# main.net
KiCad netlist of a schematic drawn in Altium Designer
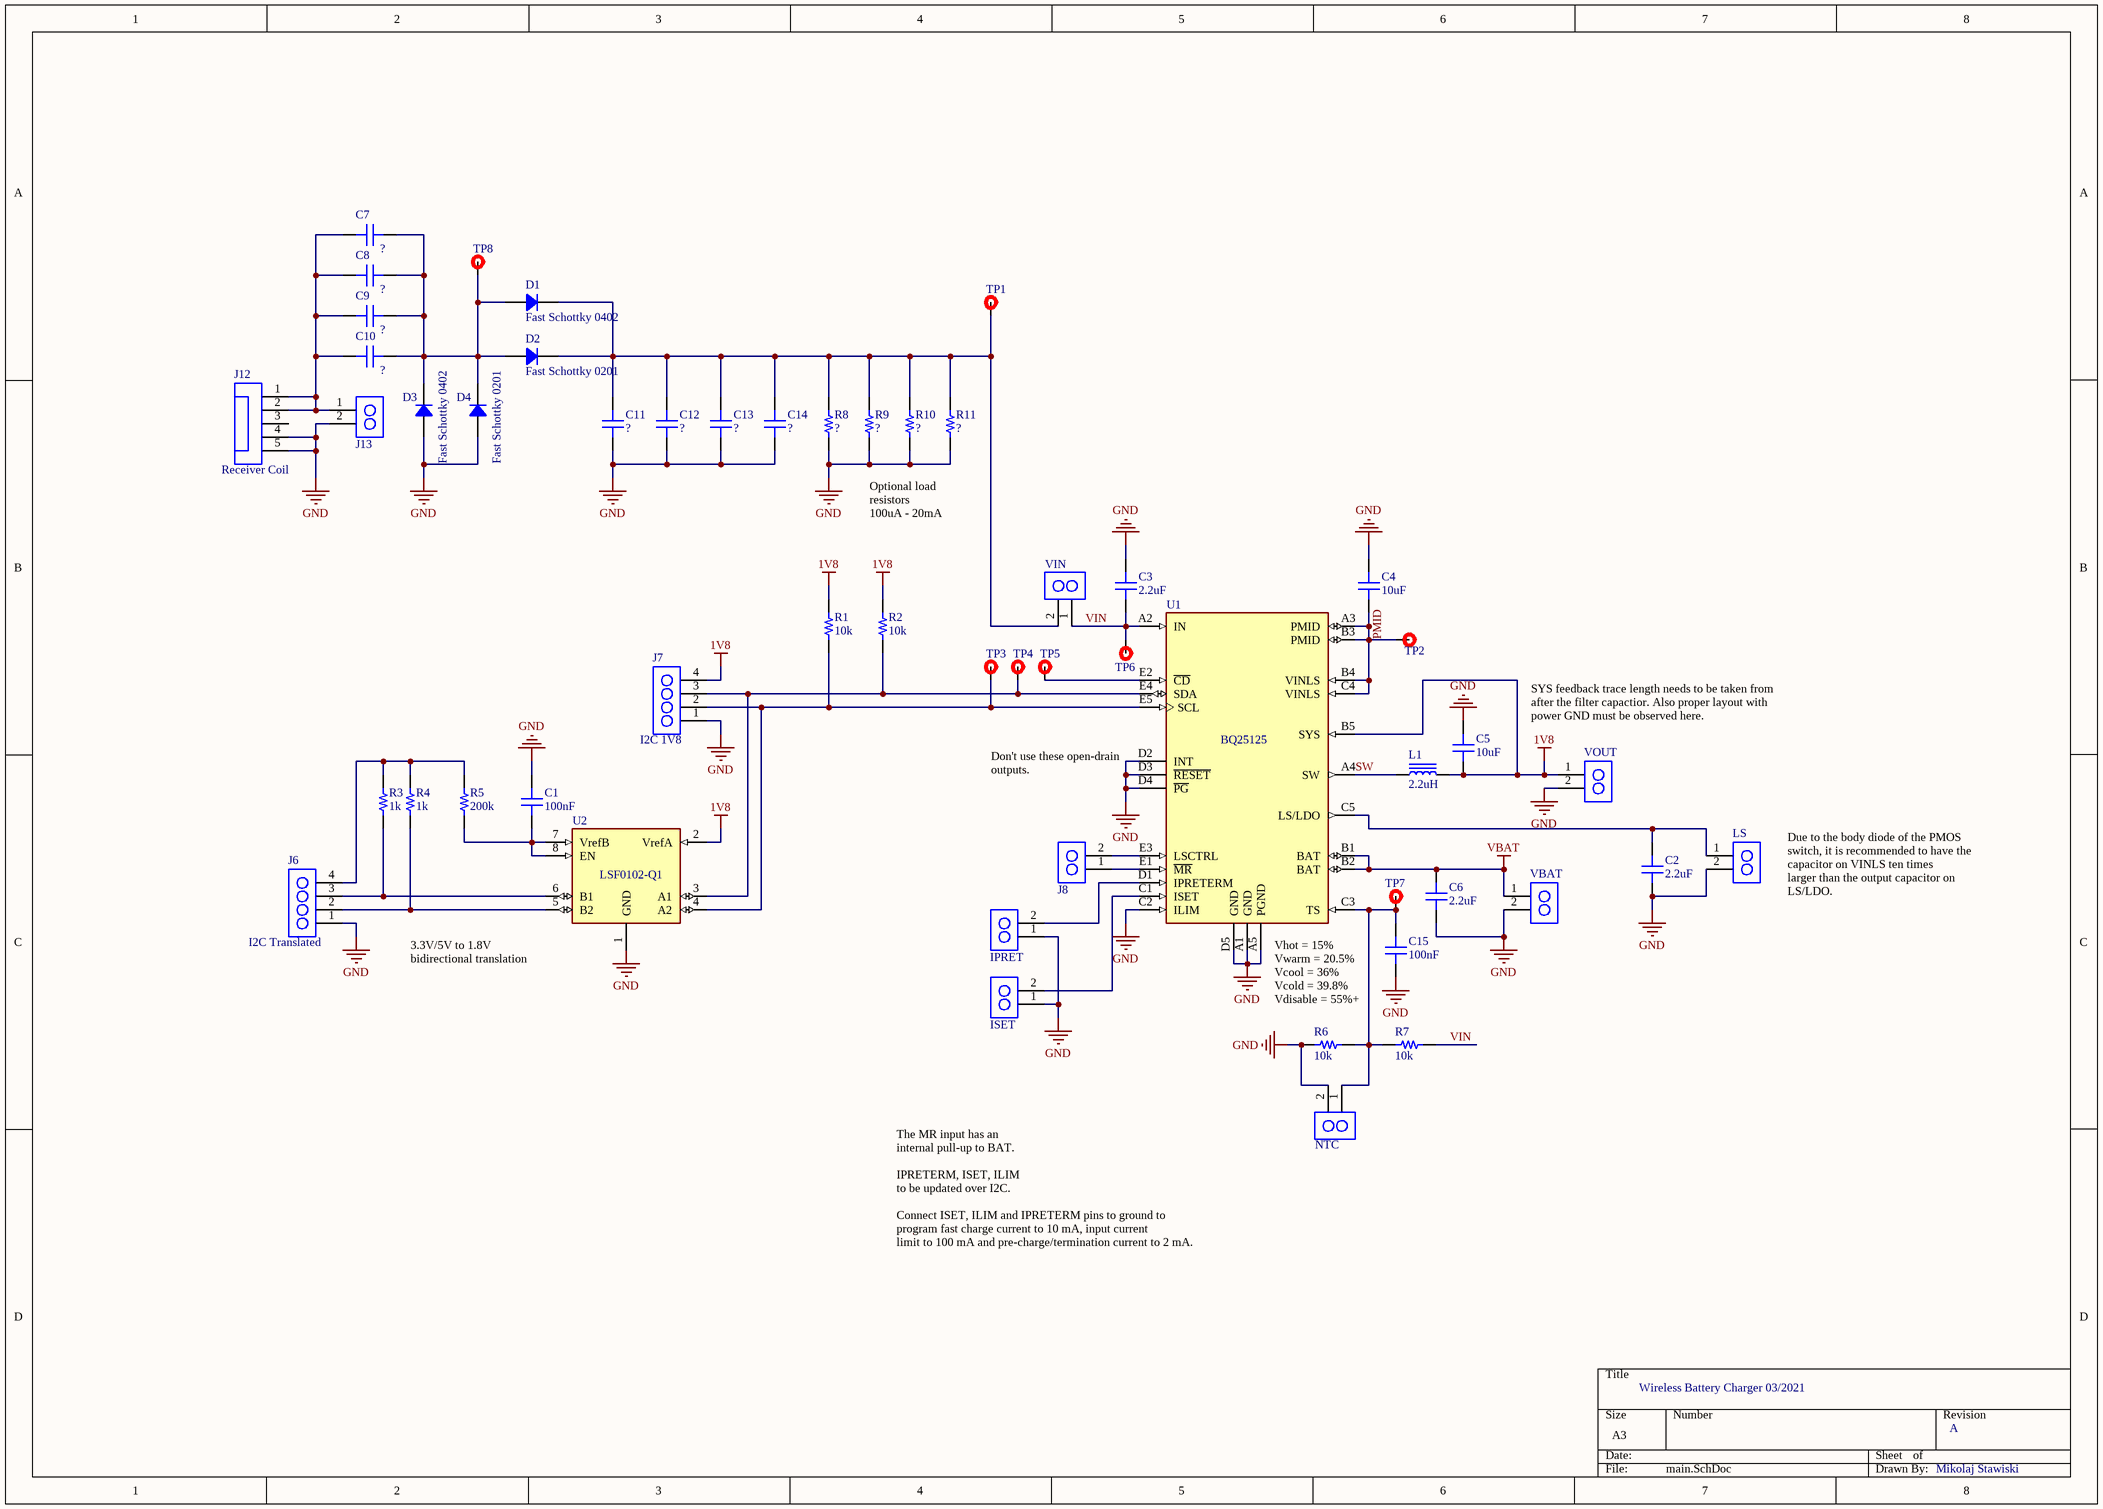
[diagram p0: main.SchDoc]

(export (version "E")
  (design (tool "Eeschema 10.0.6"))
  (components
    (comp (ref "C1")
      (value "100nF")
      (footprint "SMD_CAPACITOR_0603")
      (description "Capacitor SMT 0603")
      (libsource (lib "common") (part "CAPACITOR_0603"))
    )
    (comp (ref "C2")
      (value "2.2uF")
      (footprint "SMD_CAPACITOR_0402")
      (description "Ceramic Capacitor 2.2uF 20% 6.3V X5R 0402")
      (fields (field (name "PART NUMBER") "GRM155R60J225ME15D") (field (name "MANUFACTURER") "Murata"))
      (libsource (lib "common") (part "CAPACITOR_0402"))
    )
    (comp (ref "C3")
      (value "2.2uF")
      (footprint "SMD_CAPACITOR_0402")
      (description "Ceramic Capacitor 2.2uF 20% 6.3V X5R 0402")
      (fields (field (name "PART NUMBER") "GRM155R60J225ME15D") (field (name "MANUFACTURER") "Murata"))
      (libsource (lib "common") (part "CAPACITOR_0402"))
    )
    (comp (ref "C4")
      (value "10uF")
      (footprint "SMD_CAPACITOR_0402")
      (description "Ceramic Capacitor 10uF 20% 10V X5R 0402")
      (fields (field (name "PART NUMBER") "CL05A106MP5NUNC") (field (name "MANUFACTURER") "Samsung"))
      (libsource (lib "common") (part "CAPACITOR_0402"))
    )
    (comp (ref "C5")
      (value "10uF")
      (footprint "SMD_CAPACITOR_0402")
      (description "Ceramic Capacitor 10uF 20% 10V X5R 0402")
      (fields (field (name "PART NUMBER") "CL05A106MP5NUNC") (field (name "MANUFACTURER") "Samsung"))
      (libsource (lib "common") (part "CAPACITOR_0402"))
    )
    (comp (ref "C6")
      (value "2.2uF")
      (footprint "SMD_CAPACITOR_0402")
      (description "Ceramic Capacitor 2.2uF 20% 6.3V X5R 0402")
      (fields (field (name "PART NUMBER") "GRM155R60J225ME15D") (field (name "MANUFACTURER") "Murata"))
      (libsource (lib "common") (part "CAPACITOR_0402"))
    )
    (comp (ref "C7")
      (value "?")
      (footprint "SMD_CAPACITOR_0402")
      (description "Ceramic Capacitor 10V X5R 0402")
      (libsource (lib "common") (part "CAPACITOR_0402"))
    )
    (comp (ref "C8")
      (value "?")
      (footprint "SMD_CAPACITOR_0402")
      (description "Ceramic Capacitor 10V X5R 0402")
      (libsource (lib "common") (part "CAPACITOR_0402"))
    )
    (comp (ref "C9")
      (value "?")
      (footprint "SMD_CAPACITOR_0402")
      (description "Ceramic Capacitor 10V X5R 0402")
      (libsource (lib "common") (part "CAPACITOR_0402"))
    )
    (comp (ref "C10")
      (value "?")
      (footprint "SMD_CAPACITOR_0402")
      (description "Ceramic Capacitor 10V X5R 0402")
      (libsource (lib "common") (part "CAPACITOR_0402"))
    )
    (comp (ref "C11")
      (value "?")
      (footprint "SMD_CAPACITOR_0402")
      (description "Ceramic Capacitor 10V X5R 0402")
      (libsource (lib "common") (part "CAPACITOR_0402"))
    )
    (comp (ref "C12")
      (value "?")
      (footprint "SMD_CAPACITOR_0402")
      (description "Ceramic Capacitor 10V X5R 0402")
      (libsource (lib "common") (part "CAPACITOR_0402"))
    )
    (comp (ref "C13")
      (value "?")
      (footprint "SMD_CAPACITOR_0402")
      (description "Ceramic Capacitor 10V X5R 0402")
      (libsource (lib "common") (part "CAPACITOR_0402"))
    )
    (comp (ref "C14")
      (value "?")
      (footprint "SMD_CAPACITOR_0402")
      (description "Ceramic Capacitor 10V X5R 0402")
      (libsource (lib "common") (part "CAPACITOR_0402"))
    )
    (comp (ref "C15")
      (value "100nF")
      (footprint "SMD_CAPACITOR_0201")
      (description "Capacitor SMT 0201")
      (libsource (lib "common") (part "CAPACITOR_0201"))
    )
    (comp (ref "D1")
      (value "Fast Schottky 0402")
      (footprint "CLP1006-2L")
      (description "Diode SMT 0402")
      (fields (field (name "PART NUMBER") "VSKY05301006") (field (name "MANUFACTURER") "Vishay"))
      (libsource (lib "common") (part "DIODE_0402"))
    )
    (comp (ref "D2")
      (value "Fast Schottky 0201")
      (footprint "CLP0603-2M")
      (description "Diode SMT 0201")
      (fields (field (name "PART NUMBER") "VSKY02300603") (field (name "MANUFACTURER") "Vishay"))
      (libsource (lib "common") (part "DIODE_0201"))
    )
    (comp (ref "D3")
      (value "Fast Schottky 0402")
      (footprint "CLP1006-2L")
      (description "Diode SMT 0402")
      (fields (field (name "PART NUMBER") "VSKY05301006") (field (name "MANUFACTURER") "Vishay"))
      (libsource (lib "common") (part "DIODE_0402"))
    )
    (comp (ref "D4")
      (value "Fast Schottky 0201")
      (footprint "CLP0603-2M")
      (description "Diode SMT 0201")
      (fields (field (name "PART NUMBER") "VSKY02300603") (field (name "MANUFACTURER") "Vishay"))
      (libsource (lib "common") (part "DIODE_0201"))
    )
    (comp (ref "IPRET")
      (value "*")
      (footprint "HEADER_2PIN_0022272021")
      (description "Connector 2-pin generic")
      (libsource (lib "common") (part "CONN_2PIN"))
    )
    (comp (ref "ISET")
      (value "*")
      (footprint "HEADER_2PIN_0022272021")
      (description "Connector 2-pin generic")
      (libsource (lib "common") (part "CONN_2PIN"))
    )
    (comp (ref "J6")
      (value "I2C Translated")
      (footprint "HEADER_4PIN_0022272041")
      (description "Connector 4-pin generic")
      (libsource (lib "common") (part "CONN_4PIN"))
    )
    (comp (ref "J7")
      (value "I2C 1V8")
      (footprint "HEADER_4PIN_0022272041")
      (description "Connector 4-pin generic")
      (libsource (lib "common") (part "CONN_4PIN"))
    )
    (comp (ref "J8")
      (value "*")
      (footprint "HEADER_2PIN_0022272021")
      (description "Connector 2-pin generic")
      (libsource (lib "common") (part "CONN_2PIN"))
    )
    (comp (ref "J12")
      (value "Receiver Coil")
      (footprint "FPC_5PIN_0545500571")
      (description "FPC connector 5-pin generic")
      (libsource (lib "common") (part "CONN_FPC_5PIN"))
    )
    (comp (ref "J13")
      (value "*")
      (footprint "HEADER_2PIN_0022272021")
      (description "Connector 2-pin generic")
      (libsource (lib "common") (part "CONN_2PIN"))
    )
    (comp (ref "L1")
      (value "2.2uH")
      (footprint "SMD_INDUCTOR_0603")
      (description "Inductor fixed 2.2uH 20% 500mA 180mOhm 0603")
      (fields (field (name "PART NUMBER") "MLZ1608N2R2LT000") (field (name "MANUFACTURER") "TDK"))
      (libsource (lib "common") (part "INDUCTOR_0603"))
    )
    (comp (ref "LS")
      (value "LOAD SWITCH")
      (footprint "HEADER_2PIN_0022272021")
      (description "Connector 2-pin generic")
      (libsource (lib "common") (part "CONN_2PIN"))
    )
    (comp (ref "NTC")
      (value "NTC")
      (footprint "HEADER_2PIN_0022272021")
      (description "Connector 2-pin generic")
      (libsource (lib "common") (part "CONN_2PIN"))
    )
    (comp (ref "R1")
      (value "10k")
      (footprint "SMD_RESISTOR_0603")
      (description "Resistor SMT 0603")
      (libsource (lib "common") (part "RESISTOR_0603"))
    )
    (comp (ref "R2")
      (value "10k")
      (footprint "SMD_RESISTOR_0603")
      (description "Resistor SMT 0603")
      (libsource (lib "common") (part "RESISTOR_0603"))
    )
    (comp (ref "R3")
      (value "1k")
      (footprint "SMD_RESISTOR_0603")
      (description "Resistor SMT 0603")
      (libsource (lib "common") (part "RESISTOR_0603"))
    )
    (comp (ref "R4")
      (value "1k")
      (footprint "SMD_RESISTOR_0603")
      (description "Resistor SMT 0603")
      (libsource (lib "common") (part "RESISTOR_0603"))
    )
    (comp (ref "R5")
      (value "200k")
      (footprint "SMD_RESISTOR_0603")
      (description "Resistor SMT 0603")
      (libsource (lib "common") (part "RESISTOR_0603"))
    )
    (comp (ref "R6")
      (value "10k")
      (footprint "SMD_RESISTOR_0603")
      (description "Resistor SMT 0603")
      (libsource (lib "common") (part "RESISTOR_0603"))
    )
    (comp (ref "R7")
      (value "10k")
      (footprint "SMD_RESISTOR_0603")
      (description "Resistor SMT 0603")
      (libsource (lib "common") (part "RESISTOR_0603"))
    )
    (comp (ref "R8")
      (value "?")
      (footprint "SMD_RESISTOR_0603")
      (description "Resistor SMT 0603")
      (libsource (lib "common") (part "RESISTOR_0603"))
    )
    (comp (ref "R9")
      (value "?")
      (footprint "SMD_RESISTOR_0603")
      (description "Resistor SMT 0603")
      (libsource (lib "common") (part "RESISTOR_0603"))
    )
    (comp (ref "R10")
      (value "?")
      (footprint "SMD_RESISTOR_0402")
      (description "Resistor SMT 0402")
      (libsource (lib "common") (part "RESISTOR_0402"))
    )
    (comp (ref "R11")
      (value "?")
      (footprint "SMD_RESISTOR_0402")
      (description "Resistor SMT 0402")
      (libsource (lib "common") (part "RESISTOR_0402"))
    )
    (comp (ref "TP1")
      (value "Testpoint")
      (footprint "Testpoint 2mm")
      (description "Testpoint for measuring at the PCB")
      (libsource (lib "common") (part "Testpoint"))
    )
    (comp (ref "TP2")
      (value "Testpoint")
      (footprint "Testpoint 2mm")
      (description "Testpoint for measuring at the PCB")
      (libsource (lib "common") (part "Testpoint"))
    )
    (comp (ref "TP3")
      (value "Testpoint")
      (footprint "Testpoint 2mm")
      (description "Testpoint for measuring at the PCB")
      (libsource (lib "common") (part "Testpoint"))
    )
    (comp (ref "TP4")
      (value "Testpoint")
      (footprint "Testpoint 2mm")
      (description "Testpoint for measuring at the PCB")
      (libsource (lib "common") (part "Testpoint"))
    )
    (comp (ref "TP5")
      (value "Testpoint")
      (footprint "Testpoint 2mm")
      (description "Testpoint for measuring at the PCB")
      (libsource (lib "common") (part "Testpoint"))
    )
    (comp (ref "TP6")
      (value "Testpoint")
      (footprint "Testpoint 2mm")
      (description "Testpoint for measuring at the PCB")
      (libsource (lib "common") (part "Testpoint"))
    )
    (comp (ref "TP7")
      (value "Testpoint")
      (footprint "Testpoint 2mm")
      (description "Testpoint for measuring at the PCB")
      (libsource (lib "common") (part "Testpoint"))
    )
    (comp (ref "TP8")
      (value "Testpoint")
      (footprint "Testpoint 2mm")
      (description "Testpoint for measuring at the PCB")
      (libsource (lib "common") (part "Testpoint"))
    )
    (comp (ref "U1")
      (value "BQ25125")
      (footprint "BQ25125-DSBGA25")
      (description "BQ25125 Low IQ Highly Integrated Battery Charge Management Solution For Wearables and IoT")
      (fields (field (name "MANUFACTURER") "TI"))
      (libsource (lib "TI") (part "BQ25125"))
    )
    (comp (ref "U2")
      (value "LSF0102-Q1")
      (footprint "8-VSSOP")
      (description "Automotive 2-Channel Auto Bidirectional Multi-Voltage Level Translator")
      (fields (field (name "PART NUMBER") "LSF0102QDCURQ1") (field (name "MANUFACTURER") "TI"))
      (libsource (lib "TI") (part "LSF0102-Q1"))
    )
    (comp (ref "VBAT")
      (value "BATTERY")
      (footprint "HEADER_2PIN_0022272021")
      (description "Connector 2-pin generic")
      (libsource (lib "common") (part "CONN_2PIN"))
    )
    (comp (ref "VIN")
      (value "*")
      (footprint "HEADER_2PIN_0022272021")
      (description "Connector 2-pin generic")
      (libsource (lib "common") (part "CONN_2PIN"))
    )
    (comp (ref "VOUT")
      (value "OUT")
      (footprint "HEADER_2PIN_0022272021")
      (description "Connector 2-pin generic")
      (libsource (lib "common") (part "CONN_2PIN"))
    )
  )
  (nets
    (net (code "1") (name "/PMID") (class "Default")
      (node (ref "C4") (pin "1") (pinfunction "1_1") (pintype "passive"))
      (node (ref "TP2") (pin "1") (pintype "passive"))
      (node (ref "U1") (pin "A3") (pinfunction "PMID_A3") (pintype "bidirectional"))
      (node (ref "U1") (pin "B3") (pinfunction "PMID_B3") (pintype "bidirectional"))
      (node (ref "U1") (pin "B4") (pinfunction "VINLS_B4") (pintype "input"))
      (node (ref "U1") (pin "C4") (pinfunction "VINLS_C4") (pintype "input"))
    )
    (net (code "2") (name "/SW") (class "Default")
      (node (ref "L1") (pin "1") (pinfunction "1_1") (pintype "passive"))
      (node (ref "U1") (pin "A4") (pinfunction "SW_A4") (pintype "output"))
    )
    (net (code "3") (name "/VIN") (class "Default")
      (node (ref "C3") (pin "1") (pinfunction "1_1") (pintype "passive"))
      (node (ref "R7") (pin "1") (pinfunction "1_1") (pintype "passive"))
      (node (ref "TP6") (pin "1") (pintype "passive"))
      (node (ref "U1") (pin "A2") (pinfunction "IN_A2") (pintype "input"))
      (node (ref "VIN") (pin "1") (pinfunction "1_1") (pintype "passive"))
    )
    (net (code "4") (name "1V8") (class "Default")
      (node (ref "C5") (pin "1") (pinfunction "1_1") (pintype "passive"))
      (node (ref "J7") (pin "4") (pinfunction "4_4") (pintype "passive"))
      (node (ref "L1") (pin "2") (pinfunction "2_2") (pintype "passive"))
      (node (ref "R1") (pin "2") (pinfunction "2_2") (pintype "passive"))
      (node (ref "R2") (pin "2") (pinfunction "2_2") (pintype "passive"))
      (node (ref "U1") (pin "B5") (pinfunction "SYS_B5") (pintype "input"))
      (node (ref "U2") (pin "2") (pinfunction "VrefA_2") (pintype "input"))
      (node (ref "VOUT") (pin "1") (pinfunction "1_1") (pintype "passive"))
    )
    (net (code "5") (name "GND") (class "Default")
      (node (ref "C1") (pin "2") (pinfunction "2_2") (pintype "passive"))
      (node (ref "C11") (pin "1") (pinfunction "1_1") (pintype "passive"))
      (node (ref "C12") (pin "1") (pinfunction "1_1") (pintype "passive"))
      (node (ref "C13") (pin "1") (pinfunction "1_1") (pintype "passive"))
      (node (ref "C14") (pin "1") (pinfunction "1_1") (pintype "passive"))
      (node (ref "C15") (pin "1") (pinfunction "1_1") (pintype "passive"))
      (node (ref "C2") (pin "1") (pinfunction "1_1") (pintype "passive"))
      (node (ref "C3") (pin "2") (pinfunction "2_2") (pintype "passive"))
      (node (ref "C4") (pin "2") (pinfunction "2_2") (pintype "passive"))
      (node (ref "C5") (pin "2") (pinfunction "2_2") (pintype "passive"))
      (node (ref "C6") (pin "1") (pinfunction "1_1") (pintype "passive"))
      (node (ref "D3") (pin "1") (pinfunction "1_1") (pintype "passive"))
      (node (ref "D4") (pin "1") (pinfunction "1_1") (pintype "passive"))
      (node (ref "IPRET") (pin "1") (pinfunction "1_1") (pintype "passive"))
      (node (ref "ISET") (pin "1") (pinfunction "1_1") (pintype "passive"))
      (node (ref "J12") (pin "4") (pinfunction "4_4") (pintype "passive"))
      (node (ref "J12") (pin "5") (pinfunction "5_5") (pintype "passive"))
      (node (ref "J13") (pin "2") (pinfunction "2_2") (pintype "passive"))
      (node (ref "J6") (pin "1") (pinfunction "1_1") (pintype "passive"))
      (node (ref "J7") (pin "1") (pinfunction "1_1") (pintype "passive"))
      (node (ref "LS") (pin "2") (pinfunction "2_2") (pintype "passive"))
      (node (ref "NTC") (pin "2") (pinfunction "2_2") (pintype "passive"))
      (node (ref "R10") (pin "1") (pinfunction "1_1") (pintype "passive"))
      (node (ref "R11") (pin "1") (pinfunction "1_1") (pintype "passive"))
      (node (ref "R6") (pin "2") (pinfunction "2_2") (pintype "passive"))
      (node (ref "R8") (pin "1") (pinfunction "1_1") (pintype "passive"))
      (node (ref "R9") (pin "1") (pinfunction "1_1") (pintype "passive"))
      (node (ref "U1") (pin "A1") (pinfunction "GND_A1") (pintype "power_in"))
      (node (ref "U1") (pin "A5") (pinfunction "PGND_A5") (pintype "power_in"))
      (node (ref "U1") (pin "C2") (pinfunction "ILIM_C2") (pintype "input"))
      (node (ref "U1") (pin "D2") (pinfunction "INT_D2") (pintype "passive"))
      (node (ref "U1") (pin "D3") (pinfunction "~{RESET}_D3") (pintype "passive"))
      (node (ref "U1") (pin "D4") (pinfunction "~{PG}_D4") (pintype "passive"))
      (node (ref "U1") (pin "D5") (pinfunction "GND_D5") (pintype "power_in"))
      (node (ref "U2") (pin "1") (pinfunction "GND_1") (pintype "power_in"))
      (node (ref "VBAT") (pin "2") (pinfunction "2_2") (pintype "passive"))
      (node (ref "VOUT") (pin "2") (pinfunction "2_2") (pintype "passive"))
    )
    (net (code "6") (name "Net-(C10-Pad1)") (class "Default")
      (node (ref "C10") (pin "1") (pinfunction "1_1") (pintype "passive"))
      (node (ref "C7") (pin "1") (pinfunction "1_1") (pintype "passive"))
      (node (ref "C8") (pin "1") (pinfunction "1_1") (pintype "passive"))
      (node (ref "C9") (pin "1") (pinfunction "1_1") (pintype "passive"))
      (node (ref "D1") (pin "1") (pinfunction "1_1") (pintype "passive"))
      (node (ref "D2") (pin "1") (pinfunction "1_1") (pintype "passive"))
      (node (ref "D3") (pin "2") (pinfunction "2_2") (pintype "passive"))
      (node (ref "D4") (pin "2") (pinfunction "2_2") (pintype "passive"))
      (node (ref "TP8") (pin "1") (pintype "passive"))
    )
    (net (code "7") (name "Net-(C10-Pad2)") (class "Default")
      (node (ref "C10") (pin "2") (pinfunction "2_2") (pintype "passive"))
      (node (ref "C7") (pin "2") (pinfunction "2_2") (pintype "passive"))
      (node (ref "C8") (pin "2") (pinfunction "2_2") (pintype "passive"))
      (node (ref "C9") (pin "2") (pinfunction "2_2") (pintype "passive"))
      (node (ref "J12") (pin "1") (pinfunction "1_1") (pintype "passive"))
      (node (ref "J12") (pin "2") (pinfunction "2_2") (pintype "passive"))
      (node (ref "J13") (pin "1") (pinfunction "1_1") (pintype "passive"))
    )
    (net (code "8") (name "Net-(C11-Pad2)") (class "Default")
      (node (ref "C11") (pin "2") (pinfunction "2_2") (pintype "passive"))
      (node (ref "C12") (pin "2") (pinfunction "2_2") (pintype "passive"))
      (node (ref "C13") (pin "2") (pinfunction "2_2") (pintype "passive"))
      (node (ref "C14") (pin "2") (pinfunction "2_2") (pintype "passive"))
      (node (ref "D1") (pin "2") (pinfunction "2_2") (pintype "passive"))
      (node (ref "D2") (pin "2") (pinfunction "2_2") (pintype "passive"))
      (node (ref "R10") (pin "2") (pinfunction "2_2") (pintype "passive"))
      (node (ref "R11") (pin "2") (pinfunction "2_2") (pintype "passive"))
      (node (ref "R8") (pin "2") (pinfunction "2_2") (pintype "passive"))
      (node (ref "R9") (pin "2") (pinfunction "2_2") (pintype "passive"))
      (node (ref "TP1") (pin "1") (pintype "passive"))
      (node (ref "VIN") (pin "2") (pinfunction "2_2") (pintype "passive"))
    )
    (net (code "9") (name "Net-(J6-Pad4)") (class "Default")
      (node (ref "J6") (pin "4") (pinfunction "4_4") (pintype "passive"))
      (node (ref "R3") (pin "2") (pinfunction "2_2") (pintype "passive"))
      (node (ref "R4") (pin "2") (pinfunction "2_2") (pintype "passive"))
      (node (ref "R5") (pin "2") (pinfunction "2_2") (pintype "passive"))
    )
    (net (code "10") (name "Net-(U1-IPRETERM)") (class "Default")
      (node (ref "IPRET") (pin "2") (pinfunction "2_2") (pintype "passive"))
      (node (ref "U1") (pin "D1") (pinfunction "IPRETERM_D1") (pintype "input"))
    )
    (net (code "11") (name "Net-(U1-ISET)") (class "Default")
      (node (ref "ISET") (pin "2") (pinfunction "2_2") (pintype "passive"))
      (node (ref "U1") (pin "C1") (pinfunction "ISET_C1") (pintype "input"))
    )
    (net (code "12") (name "Net-(U1-LSCTRL)") (class "Default")
      (node (ref "J8") (pin "2") (pinfunction "2_2") (pintype "passive"))
      (node (ref "U1") (pin "E3") (pinfunction "LSCTRL_E3") (pintype "input"))
    )
    (net (code "13") (name "Net-(U1-LS{slash}LDO)") (class "Default")
      (node (ref "C2") (pin "2") (pinfunction "2_2") (pintype "passive"))
      (node (ref "LS") (pin "1") (pinfunction "1_1") (pintype "passive"))
      (node (ref "U1") (pin "C5") (pinfunction "LS/LDO_C5") (pintype "output"))
    )
    (net (code "14") (name "Net-(U1-SCL)") (class "Default")
      (node (ref "J7") (pin "2") (pinfunction "2_2") (pintype "passive"))
      (node (ref "R1") (pin "1") (pinfunction "1_1") (pintype "passive"))
      (node (ref "TP3") (pin "1") (pintype "passive"))
      (node (ref "U1") (pin "E5") (pinfunction "SCL_E5") (pintype "input"))
      (node (ref "U2") (pin "4") (pinfunction "A2_4") (pintype "bidirectional"))
    )
    (net (code "15") (name "Net-(U1-SDA)") (class "Default")
      (node (ref "J7") (pin "3") (pinfunction "3_3") (pintype "passive"))
      (node (ref "R2") (pin "1") (pinfunction "1_1") (pintype "passive"))
      (node (ref "TP4") (pin "1") (pintype "passive"))
      (node (ref "U1") (pin "E4") (pinfunction "SDA_E4") (pintype "bidirectional"))
      (node (ref "U2") (pin "3") (pinfunction "A1_3") (pintype "bidirectional"))
    )
    (net (code "16") (name "Net-(U1-TS)") (class "Default")
      (node (ref "C15") (pin "2") (pinfunction "2_2") (pintype "passive"))
      (node (ref "NTC") (pin "1") (pinfunction "1_1") (pintype "passive"))
      (node (ref "R6") (pin "1") (pinfunction "1_1") (pintype "passive"))
      (node (ref "R7") (pin "2") (pinfunction "2_2") (pintype "passive"))
      (node (ref "TP7") (pin "1") (pintype "passive"))
      (node (ref "U1") (pin "C3") (pinfunction "TS_C3") (pintype "input"))
    )
    (net (code "17") (name "Net-(U1-~{CD})") (class "Default")
      (node (ref "TP5") (pin "1") (pintype "passive"))
      (node (ref "U1") (pin "E2") (pinfunction "~{CD}_E2") (pintype "input"))
    )
    (net (code "18") (name "Net-(U1-~{MR})") (class "Default")
      (node (ref "J8") (pin "1") (pinfunction "1_1") (pintype "passive"))
      (node (ref "U1") (pin "E1") (pinfunction "~{MR}_E1") (pintype "input"))
    )
    (net (code "19") (name "Net-(U2-B1)") (class "Default")
      (node (ref "J6") (pin "3") (pinfunction "3_3") (pintype "passive"))
      (node (ref "R3") (pin "1") (pinfunction "1_1") (pintype "passive"))
      (node (ref "U2") (pin "6") (pinfunction "B1_6") (pintype "bidirectional"))
    )
    (net (code "20") (name "Net-(U2-B2)") (class "Default")
      (node (ref "J6") (pin "2") (pinfunction "2_2") (pintype "passive"))
      (node (ref "R4") (pin "1") (pinfunction "1_1") (pintype "passive"))
      (node (ref "U2") (pin "5") (pinfunction "B2_5") (pintype "bidirectional"))
    )
    (net (code "21") (name "Net-(U2-EN)") (class "Default")
      (node (ref "C1") (pin "1") (pinfunction "1_1") (pintype "passive"))
      (node (ref "R5") (pin "1") (pinfunction "1_1") (pintype "passive"))
      (node (ref "U2") (pin "7") (pinfunction "VrefB_7") (pintype "input"))
      (node (ref "U2") (pin "8") (pinfunction "EN_8") (pintype "input"))
    )
    (net (code "22") (name "VBAT") (class "Default")
      (node (ref "C6") (pin "2") (pinfunction "2_2") (pintype "passive"))
      (node (ref "U1") (pin "B1") (pinfunction "BAT_B1") (pintype "bidirectional"))
      (node (ref "U1") (pin "B2") (pinfunction "BAT_B2") (pintype "bidirectional"))
      (node (ref "VBAT") (pin "1") (pinfunction "1_1") (pintype "passive"))
    )
    (net (code "23") (name "unconnected-(J12-Pad3)") (class "Default")
      (node (ref "J12") (pin "3") (pinfunction "3_3") (pintype "passive"))
    )
  )
)
